# supertrack.net
KiCad netlist of a schematic drawn in EAGLE
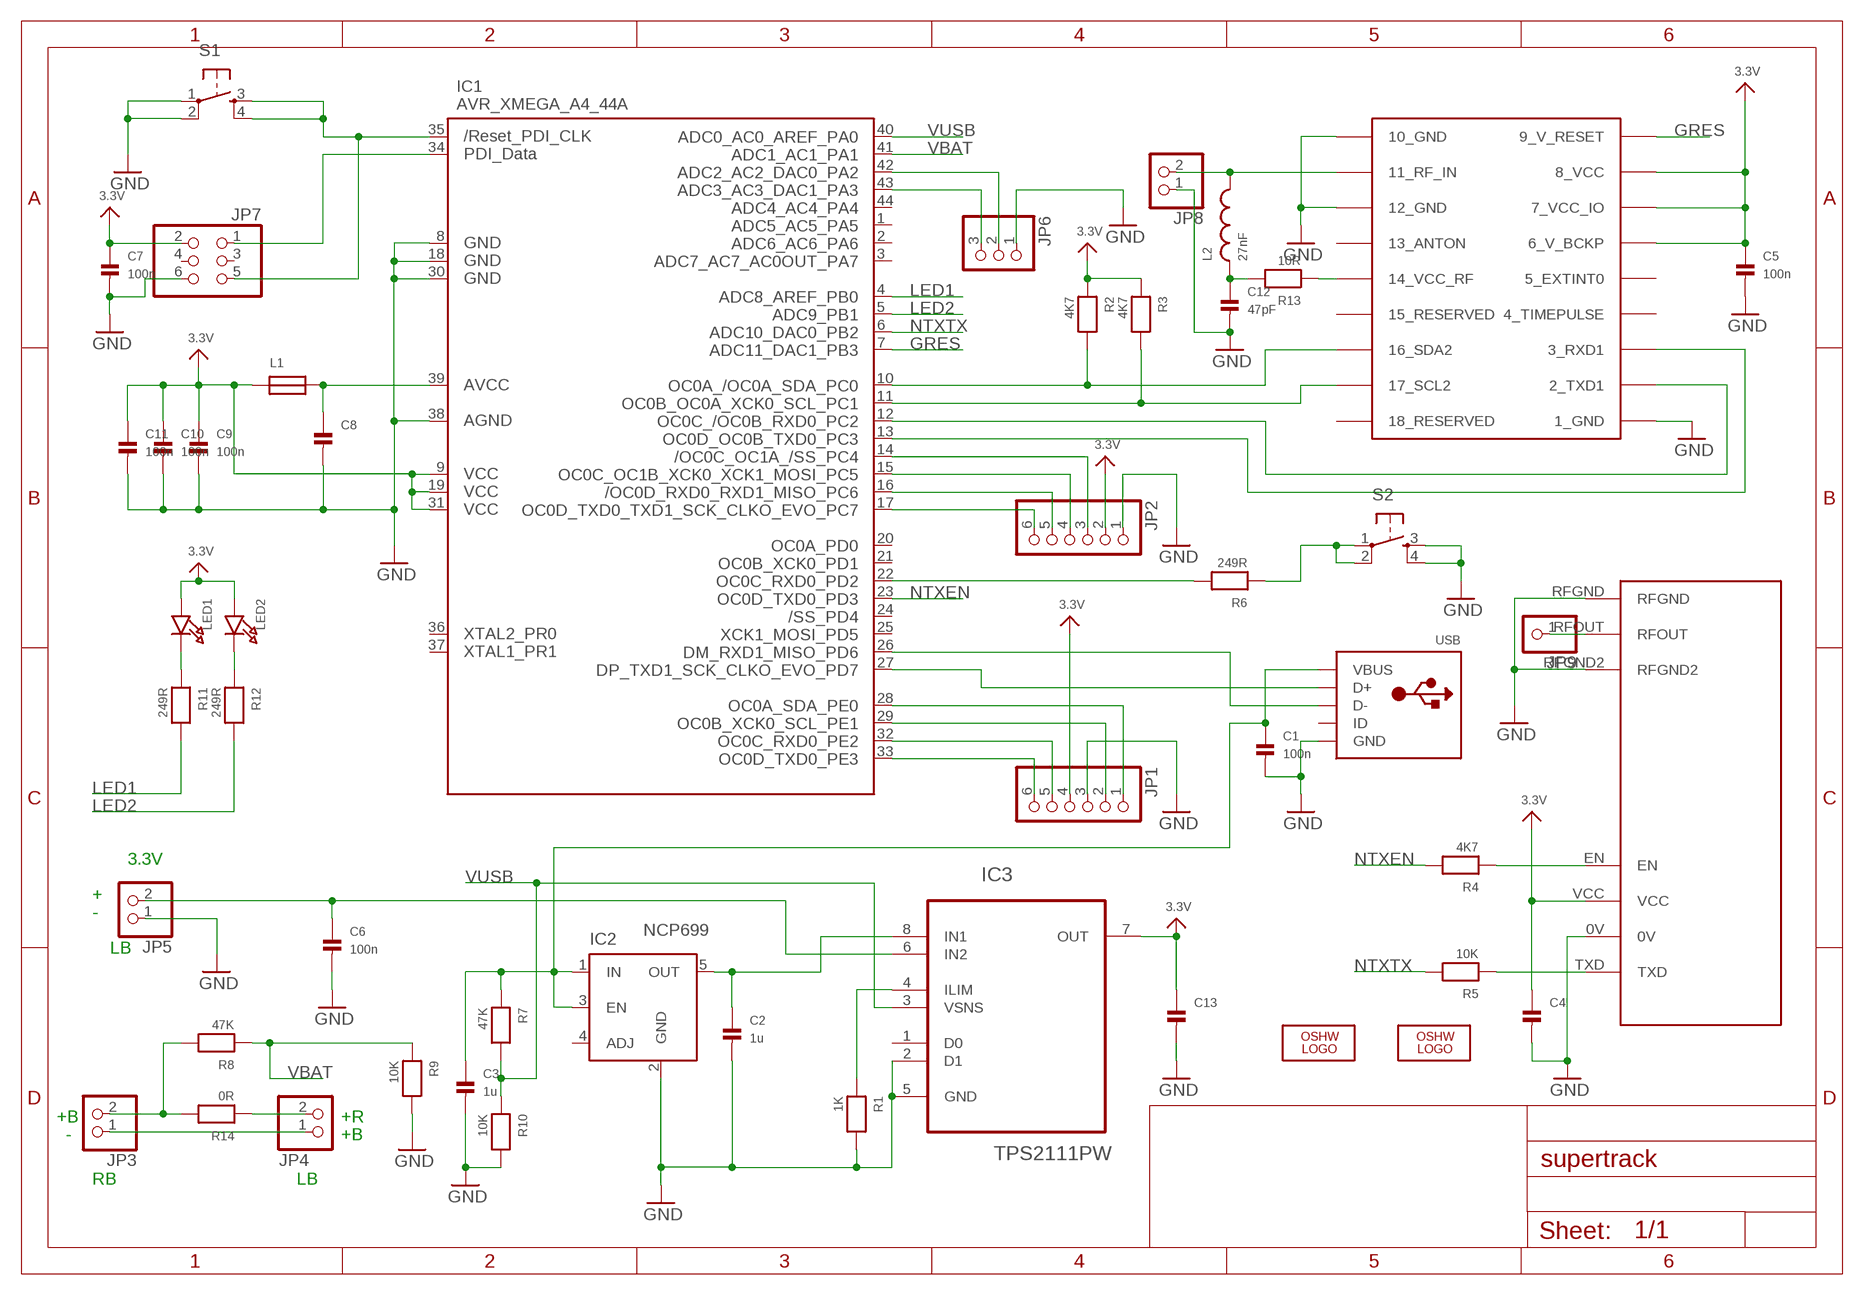
[diagram p0: schematic, sheet 1]

(export (version "E")
  (design (tool "Eeschema 10.0.6"))
  (components
    (comp (ref "C1")
      (value "100n")
      (footprint "eagle-import:0603")
      (libsource (lib "eagle-import") (part "CAP_CERAMIC0603"))
    )
    (comp (ref "C2")
      (value "1u")
      (footprint "eagle-import:0603")
      (libsource (lib "eagle-import") (part "CAP_CERAMIC0603"))
    )
    (comp (ref "C3")
      (value "1u")
      (footprint "eagle-import:0603")
      (libsource (lib "eagle-import") (part "CAP_CERAMIC0603"))
    )
    (comp (ref "C4")
      (value "CAP_CERAMIC0603")
      (footprint "eagle-import:0603")
      (libsource (lib "eagle-import") (part "CAP_CERAMIC0603"))
    )
    (comp (ref "C5")
      (value "100n")
      (footprint "eagle-import:0603")
      (libsource (lib "eagle-import") (part "CAP_CERAMIC0603"))
    )
    (comp (ref "C6")
      (value "100n")
      (footprint "eagle-import:0603")
      (libsource (lib "eagle-import") (part "CAP_CERAMIC0603"))
    )
    (comp (ref "C7")
      (value "100n")
      (footprint "eagle-import:0603")
      (libsource (lib "eagle-import") (part "CAP_CERAMIC0603"))
    )
    (comp (ref "C8")
      (value "CAP_CERAMIC0603")
      (footprint "eagle-import:0603")
      (libsource (lib "eagle-import") (part "CAP_CERAMIC0603"))
    )
    (comp (ref "C9")
      (value "100n")
      (footprint "eagle-import:0603")
      (libsource (lib "eagle-import") (part "CAP_CERAMIC0603"))
    )
    (comp (ref "C10")
      (value "100n")
      (footprint "eagle-import:0603")
      (libsource (lib "eagle-import") (part "CAP_CERAMIC0603"))
    )
    (comp (ref "C11")
      (value "100n")
      (footprint "eagle-import:0603")
      (libsource (lib "eagle-import") (part "CAP_CERAMIC0603"))
    )
    (comp (ref "C12")
      (value "47pF")
      (footprint "eagle-import:0603")
      (libsource (lib "eagle-import") (part "CAP_CERAMIC0603"))
    )
    (comp (ref "C13")
      (value "CAP_CERAMIC0603")
      (footprint "eagle-import:0603")
      (libsource (lib "eagle-import") (part "CAP_CERAMIC0603"))
    )
    (comp (ref "IC1")
      (value "AVR_XMEGA_A4_44A")
      (footprint "eagle-import:TQFP44")
      (libsource (lib "eagle-import") (part "AVR_XMEGA_A4_44A"))
    )
    (comp (ref "IC2")
      (value "NCP699")
      (footprint "eagle-import:SOT23-5")
      (fields (field (name "MF") "ALTERA CORPORATION") (field (name "MPN") "MIC5219BM5 TR"))
      (libsource (lib "eagle-import") (part "MIC5219BM5"))
    )
    (comp (ref "IC3")
      (value "TPS2111PW")
      (footprint "eagle-import:SOP65P640X120-8N")
      (libsource (lib "eagle-import") (part "TPS2111PW"))
    )
    (comp (ref "JP1")
      (value "PINHD-1X6")
      (footprint "eagle-import:1X06")
      (libsource (lib "eagle-import") (part "PINHD-1X6"))
    )
    (comp (ref "JP2")
      (value "PINHD-1X6")
      (footprint "eagle-import:1X06")
      (libsource (lib "eagle-import") (part "PINHD-1X6"))
    )
    (comp (ref "JP3")
      (value "PINHD-1X2")
      (footprint "eagle-import:1X02")
      (libsource (lib "eagle-import") (part "PINHD-1X2"))
    )
    (comp (ref "JP4")
      (value "PINHD-1X2")
      (footprint "eagle-import:1X02")
      (libsource (lib "eagle-import") (part "PINHD-1X2"))
    )
    (comp (ref "JP5")
      (value "PINHD-1X2")
      (footprint "eagle-import:1X02")
      (libsource (lib "eagle-import") (part "PINHD-1X2"))
    )
    (comp (ref "JP6")
      (value "PINHD-1X3")
      (footprint "eagle-import:1X03")
      (libsource (lib "eagle-import") (part "PINHD-1X3"))
    )
    (comp (ref "JP7")
      (value "PINHD-2X3")
      (footprint "eagle-import:2X03")
      (libsource (lib "eagle-import") (part "PINHD-2X3"))
    )
    (comp (ref "JP8")
      (value "HEADER-1X2ROUND")
      (footprint "eagle-import:1X02_ROUND")
      (libsource (lib "eagle-import") (part "HEADER-1X2ROUND"))
    )
    (comp (ref "JP9")
      (value "HEADER-1X1ROUND")
      (footprint "eagle-import:1X01_ROUND")
      (libsource (lib "eagle-import") (part "HEADER-1X1ROUND"))
    )
    (comp (ref "L1")
      (value "FERRITE")
      (footprint "eagle-import:0603")
      (libsource (lib "eagle-import") (part "FERRITE"))
    )
    (comp (ref "L2")
      (value "27nF")
      (footprint "eagle-import:0603")
      (libsource (lib "eagle-import") (part "INDUCTOR0603"))
    )
    (comp (ref "LED1")
      (value "LED0603")
      (footprint "eagle-import:CHIPLED_0603")
      (libsource (lib "eagle-import") (part "LED0603"))
    )
    (comp (ref "LED2")
      (value "LED0603")
      (footprint "eagle-import:CHIPLED_0603")
      (libsource (lib "eagle-import") (part "LED0603"))
    )
    (comp (ref "LOGO1")
      (value "OSHW_LOGO_8MILX0150-NT")
      (footprint "eagle-import:OSHW_8X150_NOTEXT")
      (libsource (lib "eagle-import") (part "OSHW_LOGO_8MILX0150-NT"))
    )
    (comp (ref "LOGO2")
      (value "OSHW_LOGO_8MILX0100-NT")
      (footprint "eagle-import:OSHW_8X100_NOTEXT")
      (libsource (lib "eagle-import") (part "OSHW_LOGO_8MILX0100-NT"))
    )
    (comp (ref "R1")
      (value "1K")
      (footprint "eagle-import:0603")
      (libsource (lib "eagle-import") (part "RESISTOR0603"))
    )
    (comp (ref "R2")
      (value "4K7")
      (footprint "eagle-import:0603")
      (libsource (lib "eagle-import") (part "RESISTOR0603"))
    )
    (comp (ref "R3")
      (value "4K7")
      (footprint "eagle-import:0603")
      (libsource (lib "eagle-import") (part "RESISTOR0603"))
    )
    (comp (ref "R4")
      (value "4K7")
      (footprint "eagle-import:0603")
      (libsource (lib "eagle-import") (part "RESISTOR0603"))
    )
    (comp (ref "R5")
      (value "10K")
      (footprint "eagle-import:0603")
      (libsource (lib "eagle-import") (part "RESISTOR0603"))
    )
    (comp (ref "R6")
      (value "249R")
      (footprint "eagle-import:0603")
      (libsource (lib "eagle-import") (part "RESISTOR0603"))
    )
    (comp (ref "R7")
      (value "47K")
      (footprint "eagle-import:0603")
      (libsource (lib "eagle-import") (part "RESISTOR0603"))
    )
    (comp (ref "R8")
      (value "47K")
      (footprint "eagle-import:0603")
      (libsource (lib "eagle-import") (part "RESISTOR0603"))
    )
    (comp (ref "R9")
      (value "10K")
      (footprint "eagle-import:0603")
      (libsource (lib "eagle-import") (part "RESISTOR0603"))
    )
    (comp (ref "R10")
      (value "10K")
      (footprint "eagle-import:0603")
      (libsource (lib "eagle-import") (part "RESISTOR0603"))
    )
    (comp (ref "R11")
      (value "249R")
      (footprint "eagle-import:0603")
      (libsource (lib "eagle-import") (part "RESISTOR0603"))
    )
    (comp (ref "R12")
      (value "249R")
      (footprint "eagle-import:0603")
      (libsource (lib "eagle-import") (part "RESISTOR0603"))
    )
    (comp (ref "R13")
      (value "10R")
      (footprint "eagle-import:0603")
      (libsource (lib "eagle-import") (part "RESISTOR0603"))
    )
    (comp (ref "R14")
      (value "0R")
      (footprint "eagle-import:0603")
      (libsource (lib "eagle-import") (part "RESISTOR0603"))
    )
    (comp (ref "S1")
      (value "TAC_SWITCHSMD")
      (footprint "eagle-import:TACTILE_SWITCH_SMD")
      (libsource (lib "eagle-import") (part "TAC_SWITCHSMD"))
    )
    (comp (ref "S2")
      (value "TAC_SWITCHSMD")
      (footprint "eagle-import:TACTILE_SWITCH_SMD")
      (libsource (lib "eagle-import") (part "TAC_SWITCHSMD"))
    )
    (comp (ref "U$1")
      (value "NTX2")
      (footprint "eagle-import:NTX2")
      (libsource (lib "eagle-import") (part "NTX2"))
    )
    (comp (ref "U$2")
      (value "UBLOX_MAX")
      (footprint "eagle-import:UBLOX_MAX")
      (libsource (lib "eagle-import") (part "UBLOX_MAX"))
    )
    (comp (ref "USB")
      (value "USBMINIB")
      (footprint "eagle-import:USB-MINIB")
      (libsource (lib "eagle-import") (part "USBMINIB"))
    )
  )
  (nets
    (net (code "1") (name "/GRES") (class "Default")
      (node (ref "IC1") (pin "7") (pinfunction "PB3_7") (pintype "bidirectional"))
      (node (ref "U$2") (pin "9_V_RESET") (pinfunction "9_V_RESET_9_V_RESET") (pintype "power_in"))
    )
    (net (code "2") (name "/LED1") (class "Default")
      (node (ref "IC1") (pin "4") (pinfunction "PB0_4") (pintype "bidirectional"))
      (node (ref "R11") (pin "2") (pinfunction "2_2") (pintype "passive"))
    )
    (net (code "3") (name "/LED2") (class "Default")
      (node (ref "IC1") (pin "5") (pinfunction "PB1_5") (pintype "bidirectional"))
      (node (ref "R12") (pin "2") (pinfunction "2_2") (pintype "passive"))
    )
    (net (code "4") (name "/NTXEN") (class "Default")
      (node (ref "IC1") (pin "23") (pinfunction "PD3_23") (pintype "bidirectional"))
      (node (ref "R4") (pin "2") (pinfunction "2_2") (pintype "passive"))
    )
    (net (code "5") (name "/NTXTX") (class "Default")
      (node (ref "IC1") (pin "6") (pinfunction "PB2_6") (pintype "bidirectional"))
      (node (ref "R5") (pin "2") (pinfunction "2_2") (pintype "passive"))
    )
    (net (code "6") (name "/VBAT") (class "Default")
      (node (ref "IC1") (pin "41") (pinfunction "PA1_41") (pintype "bidirectional"))
      (node (ref "R8") (pin "1") (pinfunction "1_1") (pintype "passive"))
      (node (ref "R9") (pin "1") (pinfunction "1_1") (pintype "passive"))
    )
    (net (code "7") (name "/VUSB") (class "Default")
      (node (ref "IC1") (pin "40") (pinfunction "PA0_40") (pintype "bidirectional"))
      (node (ref "IC3") (pin "3") (pinfunction "VSNS_3") (pintype "input"))
      (node (ref "R10") (pin "1") (pinfunction "1_1") (pintype "passive"))
      (node (ref "R7") (pin "2") (pinfunction "2_2") (pintype "passive"))
    )
    (net (code "8") (name "3.3V") (class "Default")
      (node (ref "C10") (pin "1") (pinfunction "P$1_1") (pintype "passive"))
      (node (ref "C11") (pin "1") (pinfunction "P$1_1") (pintype "passive"))
      (node (ref "C13") (pin "1") (pinfunction "P$1_1") (pintype "passive"))
      (node (ref "C4") (pin "1") (pinfunction "P$1_1") (pintype "passive"))
      (node (ref "C5") (pin "1") (pinfunction "P$1_1") (pintype "passive"))
      (node (ref "C7") (pin "1") (pinfunction "P$1_1") (pintype "passive"))
      (node (ref "C9") (pin "1") (pinfunction "P$1_1") (pintype "passive"))
      (node (ref "IC1") (pin "19") (pinfunction "VCC2_19") (pintype "bidirectional"))
      (node (ref "IC1") (pin "31") (pinfunction "VCC3_31") (pintype "bidirectional"))
      (node (ref "IC1") (pin "9") (pinfunction "VCC1_9") (pintype "bidirectional"))
      (node (ref "IC3") (pin "7") (pinfunction "OUT_7") (pintype "output"))
      (node (ref "JP1") (pin "4") (pinfunction "4_4") (pintype "passive"))
      (node (ref "JP2") (pin "2") (pinfunction "2_2") (pintype "passive"))
      (node (ref "JP7") (pin "2") (pinfunction "2_2") (pintype "passive"))
      (node (ref "L1") (pin "1") (pinfunction "P$1_1") (pintype "bidirectional"))
      (node (ref "LED1") (pin "A") (pinfunction "A_A") (pintype "passive"))
      (node (ref "LED2") (pin "A") (pinfunction "A_A") (pintype "passive"))
      (node (ref "R2") (pin "1") (pinfunction "1_1") (pintype "passive"))
      (node (ref "R3") (pin "1") (pinfunction "1_1") (pintype "passive"))
      (node (ref "U$1") (pin "VCC") (pinfunction "VCC_VCC") (pintype "bidirectional"))
      (node (ref "U$2") (pin "6_V_BCKP") (pinfunction "6_V_BCKP_6_V_BCKP") (pintype "bidirectional"))
      (node (ref "U$2") (pin "7_VCC_IO") (pinfunction "7_VCC_IO_7_VCC_IO") (pintype "power_in"))
      (node (ref "U$2") (pin "8_VCC") (pinfunction "8_VCC_8_VCC") (pintype "power_in"))
    )
    (net (code "9") (name "GND") (class "Default")
      (node (ref "C1") (pin "2") (pinfunction "P$2_2") (pintype "passive"))
      (node (ref "C10") (pin "2") (pinfunction "P$2_2") (pintype "passive"))
      (node (ref "C11") (pin "2") (pinfunction "P$2_2") (pintype "passive"))
      (node (ref "C12") (pin "2") (pinfunction "P$2_2") (pintype "passive"))
      (node (ref "C13") (pin "2") (pinfunction "P$2_2") (pintype "passive"))
      (node (ref "C2") (pin "2") (pinfunction "P$2_2") (pintype "passive"))
      (node (ref "C3") (pin "2") (pinfunction "P$2_2") (pintype "passive"))
      (node (ref "C4") (pin "2") (pinfunction "P$2_2") (pintype "passive"))
      (node (ref "C5") (pin "2") (pinfunction "P$2_2") (pintype "passive"))
      (node (ref "C6") (pin "2") (pinfunction "P$2_2") (pintype "passive"))
      (node (ref "C7") (pin "2") (pinfunction "P$2_2") (pintype "passive"))
      (node (ref "C8") (pin "2") (pinfunction "P$2_2") (pintype "passive"))
      (node (ref "C9") (pin "2") (pinfunction "P$2_2") (pintype "passive"))
      (node (ref "IC1") (pin "18") (pinfunction "GND2_18") (pintype "bidirectional"))
      (node (ref "IC1") (pin "30") (pinfunction "GND3_30") (pintype "bidirectional"))
      (node (ref "IC1") (pin "38") (pinfunction "AGND_38") (pintype "bidirectional"))
      (node (ref "IC1") (pin "8") (pinfunction "GND1_8") (pintype "bidirectional"))
      (node (ref "IC2") (pin "2") (pinfunction "GND_2") (pintype "power_in"))
      (node (ref "IC3") (pin "2") (pinfunction "D1_2") (pintype "input"))
      (node (ref "IC3") (pin "5") (pinfunction "GND_5") (pintype "passive"))
      (node (ref "JP1") (pin "3") (pinfunction "3_3") (pintype "passive"))
      (node (ref "JP2") (pin "1") (pinfunction "1_1") (pintype "passive"))
      (node (ref "JP5") (pin "1") (pinfunction "1_1") (pintype "passive"))
      (node (ref "JP6") (pin "1") (pinfunction "1_1") (pintype "passive"))
      (node (ref "JP7") (pin "6") (pinfunction "6_6") (pintype "passive"))
      (node (ref "JP8") (pin "1") (pinfunction "1_1") (pintype "passive"))
      (node (ref "R1") (pin "2") (pinfunction "2_2") (pintype "passive"))
      (node (ref "R10") (pin "2") (pinfunction "2_2") (pintype "passive"))
      (node (ref "R9") (pin "2") (pinfunction "2_2") (pintype "passive"))
      (node (ref "S1") (pin "1") (pinfunction "1_1") (pintype "passive"))
      (node (ref "S1") (pin "2") (pinfunction "2_2") (pintype "passive"))
      (node (ref "S2") (pin "3") (pinfunction "3_3") (pintype "passive"))
      (node (ref "S2") (pin "4") (pinfunction "4_4") (pintype "passive"))
      (node (ref "U$1") (pin "0V") (pinfunction "0V_0V") (pintype "bidirectional"))
      (node (ref "U$1") (pin "RFGND") (pinfunction "RFGND_RFGND") (pintype "bidirectional"))
      (node (ref "U$1") (pin "RFGND2") (pinfunction "RFGND2_RFGND2") (pintype "bidirectional"))
      (node (ref "U$2") (pin "10_GND") (pinfunction "10_GND_10_GND") (pintype "power_in"))
      (node (ref "U$2") (pin "12_GND") (pinfunction "12_GND_12_GND") (pintype "power_in"))
      (node (ref "U$2") (pin "1_GND") (pinfunction "1_GND_1_GND") (pintype "power_in"))
      (node (ref "USB") (pin "GND") (pinfunction "GND_GND") (pintype "power_in"))
    )
    (net (code "10") (name "Net-(C1-P$1)") (class "Default")
      (node (ref "C1") (pin "1") (pinfunction "P$1_1") (pintype "passive"))
      (node (ref "C3") (pin "1") (pinfunction "P$1_1") (pintype "passive"))
      (node (ref "IC2") (pin "1") (pinfunction "IN_1") (pintype "input"))
      (node (ref "IC2") (pin "3") (pinfunction "EN_3") (pintype "input"))
      (node (ref "R7") (pin "1") (pinfunction "1_1") (pintype "passive"))
      (node (ref "USB") (pin "VBUS") (pinfunction "VBUS_VBUS") (pintype "power_in"))
    )
    (net (code "11") (name "Net-(C2-P$1)") (class "Default")
      (node (ref "C2") (pin "1") (pinfunction "P$1_1") (pintype "passive"))
      (node (ref "IC2") (pin "5") (pinfunction "OUT_5") (pintype "output"))
      (node (ref "IC3") (pin "8") (pinfunction "IN1_8") (pintype "power_in"))
    )
    (net (code "12") (name "Net-(C6-P$1)") (class "Default")
      (node (ref "C6") (pin "1") (pinfunction "P$1_1") (pintype "passive"))
      (node (ref "IC3") (pin "6") (pinfunction "IN2_6") (pintype "power_in"))
      (node (ref "JP5") (pin "2") (pinfunction "2_2") (pintype "passive"))
    )
    (net (code "13") (name "Net-(C8-P$1)") (class "Default")
      (node (ref "C8") (pin "1") (pinfunction "P$1_1") (pintype "passive"))
      (node (ref "IC1") (pin "39") (pinfunction "AVCC_39") (pintype "bidirectional"))
      (node (ref "L1") (pin "2") (pinfunction "P$2_2") (pintype "bidirectional"))
    )
    (net (code "14") (name "Net-(C12-P$1)") (class "Default")
      (node (ref "C12") (pin "1") (pinfunction "P$1_1") (pintype "passive"))
      (node (ref "L2") (pin "1") (pinfunction "1_1") (pintype "passive"))
      (node (ref "R13") (pin "2") (pinfunction "2_2") (pintype "passive"))
    )
    (net (code "15") (name "Net-(IC1-PA2)") (class "Default")
      (node (ref "IC1") (pin "42") (pinfunction "PA2_42") (pintype "bidirectional"))
      (node (ref "JP6") (pin "2") (pinfunction "2_2") (pintype "passive"))
    )
    (net (code "16") (name "Net-(IC1-PA3)") (class "Default")
      (node (ref "IC1") (pin "43") (pinfunction "PA3_43") (pintype "bidirectional"))
      (node (ref "JP6") (pin "3") (pinfunction "3_3") (pintype "passive"))
    )
    (net (code "17") (name "Net-(IC1-PC0)") (class "Default")
      (node (ref "IC1") (pin "10") (pinfunction "PC0_10") (pintype "bidirectional"))
      (node (ref "R2") (pin "2") (pinfunction "2_2") (pintype "passive"))
      (node (ref "U$2") (pin "16_SDA2") (pinfunction "16_SDA2_16_SDA2") (pintype "bidirectional"))
    )
    (net (code "18") (name "Net-(IC1-PC1)") (class "Default")
      (node (ref "IC1") (pin "11") (pinfunction "PC1_11") (pintype "bidirectional"))
      (node (ref "R3") (pin "2") (pinfunction "2_2") (pintype "passive"))
      (node (ref "U$2") (pin "17_SCL2") (pinfunction "17_SCL2_17_SCL2") (pintype "bidirectional"))
    )
    (net (code "19") (name "Net-(IC1-PC2)") (class "Default")
      (node (ref "IC1") (pin "12") (pinfunction "PC2_12") (pintype "bidirectional"))
      (node (ref "U$2") (pin "2_TXD1") (pinfunction "2_TXD1_2_TXD1") (pintype "bidirectional"))
    )
    (net (code "20") (name "Net-(IC1-PC3)") (class "Default")
      (node (ref "IC1") (pin "13") (pinfunction "PC3_13") (pintype "bidirectional"))
      (node (ref "U$2") (pin "3_RXD1") (pinfunction "3_RXD1_3_RXD1") (pintype "bidirectional"))
    )
    (net (code "21") (name "Net-(IC1-PC4)") (class "Default")
      (node (ref "IC1") (pin "14") (pinfunction "PC4_14") (pintype "bidirectional"))
      (node (ref "JP2") (pin "3") (pinfunction "3_3") (pintype "passive"))
    )
    (net (code "22") (name "Net-(IC1-PC5)") (class "Default")
      (node (ref "IC1") (pin "15") (pinfunction "PC5_15") (pintype "bidirectional"))
      (node (ref "JP2") (pin "4") (pinfunction "4_4") (pintype "passive"))
    )
    (net (code "23") (name "Net-(IC1-PC6)") (class "Default")
      (node (ref "IC1") (pin "16") (pinfunction "PC6_16") (pintype "bidirectional"))
      (node (ref "JP2") (pin "5") (pinfunction "5_5") (pintype "passive"))
    )
    (net (code "24") (name "Net-(IC1-PC7)") (class "Default")
      (node (ref "IC1") (pin "17") (pinfunction "PC7_17") (pintype "bidirectional"))
      (node (ref "JP2") (pin "6") (pinfunction "6_6") (pintype "passive"))
    )
    (net (code "25") (name "Net-(IC1-PD2)") (class "Default")
      (node (ref "IC1") (pin "22") (pinfunction "PD2_22") (pintype "bidirectional"))
      (node (ref "R6") (pin "2") (pinfunction "2_2") (pintype "passive"))
    )
    (net (code "26") (name "Net-(IC1-PD6)") (class "Default")
      (node (ref "IC1") (pin "26") (pinfunction "PD6_26") (pintype "bidirectional"))
      (node (ref "USB") (pin "D-") (pinfunction "D-_D-") (pintype "bidirectional"))
    )
    (net (code "27") (name "Net-(IC1-PD7)") (class "Default")
      (node (ref "IC1") (pin "27") (pinfunction "PD7_27") (pintype "bidirectional"))
      (node (ref "USB") (pin "D+") (pinfunction "D+_D+") (pintype "bidirectional"))
    )
    (net (code "28") (name "Net-(IC1-PDI_DATA)") (class "Default")
      (node (ref "IC1") (pin "34") (pinfunction "PDI_DATA_34") (pintype "bidirectional"))
      (node (ref "JP7") (pin "1") (pinfunction "1_1") (pintype "passive"))
    )
    (net (code "29") (name "Net-(IC1-PE0)") (class "Default")
      (node (ref "IC1") (pin "28") (pinfunction "PE0_28") (pintype "bidirectional"))
      (node (ref "JP1") (pin "1") (pinfunction "1_1") (pintype "passive"))
    )
    (net (code "30") (name "Net-(IC1-PE1)") (class "Default")
      (node (ref "IC1") (pin "29") (pinfunction "PE1_29") (pintype "bidirectional"))
      (node (ref "JP1") (pin "2") (pinfunction "2_2") (pintype "passive"))
    )
    (net (code "31") (name "Net-(IC1-PE2)") (class "Default")
      (node (ref "IC1") (pin "32") (pinfunction "PE2_32") (pintype "bidirectional"))
      (node (ref "JP1") (pin "5") (pinfunction "5_5") (pintype "passive"))
    )
    (net (code "32") (name "Net-(IC1-PE3)") (class "Default")
      (node (ref "IC1") (pin "33") (pinfunction "PE3_33") (pintype "bidirectional"))
      (node (ref "JP1") (pin "6") (pinfunction "6_6") (pintype "passive"))
    )
    (net (code "33") (name "Net-(IC1-RESET)") (class "Default")
      (node (ref "IC1") (pin "35") (pinfunction "RESET_35") (pintype "bidirectional"))
      (node (ref "JP7") (pin "5") (pinfunction "5_5") (pintype "passive"))
      (node (ref "S1") (pin "3") (pinfunction "3_3") (pintype "passive"))
      (node (ref "S1") (pin "4") (pinfunction "4_4") (pintype "passive"))
    )
    (net (code "34") (name "Net-(IC3-ILIM)") (class "Default")
      (node (ref "IC3") (pin "4") (pinfunction "ILIM_4") (pintype "input"))
      (node (ref "R1") (pin "1") (pinfunction "1_1") (pintype "passive"))
    )
    (net (code "35") (name "Net-(JP3-Pad1)") (class "Default")
      (node (ref "JP3") (pin "1") (pinfunction "1_1") (pintype "passive"))
      (node (ref "JP4") (pin "1") (pinfunction "1_1") (pintype "passive"))
    )
    (net (code "36") (name "Net-(JP3-Pad2)") (class "Default")
      (node (ref "JP3") (pin "2") (pinfunction "2_2") (pintype "passive"))
      (node (ref "R14") (pin "2") (pinfunction "2_2") (pintype "passive"))
      (node (ref "R8") (pin "2") (pinfunction "2_2") (pintype "passive"))
    )
    (net (code "37") (name "Net-(JP4-Pad2)") (class "Default")
      (node (ref "JP4") (pin "2") (pinfunction "2_2") (pintype "passive"))
      (node (ref "R14") (pin "1") (pinfunction "1_1") (pintype "passive"))
    )
    (net (code "38") (name "Net-(JP8-Pad2)") (class "Default")
      (node (ref "JP8") (pin "2") (pinfunction "2_2") (pintype "passive"))
      (node (ref "L2") (pin "2") (pinfunction "2_2") (pintype "passive"))
      (node (ref "U$2") (pin "11_RF_IN") (pinfunction "11_RF_IN_11_RF_IN") (pintype "bidirectional"))
    )
    (net (code "39") (name "Net-(JP9-Pad1)") (class "Default")
      (node (ref "JP9") (pin "1") (pinfunction "1_1") (pintype "passive"))
      (node (ref "U$1") (pin "RFOUT") (pinfunction "RFOUT_RFOUT") (pintype "bidirectional"))
    )
    (net (code "40") (name "Net-(LED1-PadC)") (class "Default")
      (node (ref "LED1") (pin "C") (pinfunction "C_C") (pintype "passive"))
      (node (ref "R11") (pin "1") (pinfunction "1_1") (pintype "passive"))
    )
    (net (code "41") (name "Net-(LED2-PadC)") (class "Default")
      (node (ref "LED2") (pin "C") (pinfunction "C_C") (pintype "passive"))
      (node (ref "R12") (pin "1") (pinfunction "1_1") (pintype "passive"))
    )
    (net (code "42") (name "Net-(R4-Pad1)") (class "Default")
      (node (ref "R4") (pin "1") (pinfunction "1_1") (pintype "passive"))
      (node (ref "U$1") (pin "EN") (pinfunction "EN_EN") (pintype "bidirectional"))
    )
    (net (code "43") (name "Net-(R5-Pad1)") (class "Default")
      (node (ref "R5") (pin "1") (pinfunction "1_1") (pintype "passive"))
      (node (ref "U$1") (pin "TXD") (pinfunction "TXD_TXD") (pintype "bidirectional"))
    )
    (net (code "44") (name "Net-(R6-Pad1)") (class "Default")
      (node (ref "R6") (pin "1") (pinfunction "1_1") (pintype "passive"))
      (node (ref "S2") (pin "1") (pinfunction "1_1") (pintype "passive"))
      (node (ref "S2") (pin "2") (pinfunction "2_2") (pintype "passive"))
    )
    (net (code "45") (name "Net-(R13-Pad1)") (class "Default")
      (node (ref "R13") (pin "1") (pinfunction "1_1") (pintype "passive"))
      (node (ref "U$2") (pin "14_VCC_RF") (pinfunction "14_VCC_RF_14_VCC_RF") (pintype "bidirectional"))
    )
    (net (code "46") (name "unconnected-(IC1-PA4-Pad44)") (class "Default")
      (node (ref "IC1") (pin "44") (pinfunction "PA4_44") (pintype "bidirectional"))
    )
    (net (code "47") (name "unconnected-(IC1-PA5-Pad1)") (class "Default")
      (node (ref "IC1") (pin "1") (pinfunction "PA5_1") (pintype "bidirectional"))
    )
    (net (code "48") (name "unconnected-(IC1-PA6-Pad2)") (class "Default")
      (node (ref "IC1") (pin "2") (pinfunction "PA6_2") (pintype "bidirectional"))
    )
    (net (code "49") (name "unconnected-(IC1-PA7-Pad3)") (class "Default")
      (node (ref "IC1") (pin "3") (pinfunction "PA7_3") (pintype "bidirectional"))
    )
    (net (code "50") (name "unconnected-(IC1-PD0-Pad20)") (class "Default")
      (node (ref "IC1") (pin "20") (pinfunction "PD0_20") (pintype "bidirectional"))
    )
    (net (code "51") (name "unconnected-(IC1-PD1-Pad21)") (class "Default")
      (node (ref "IC1") (pin "21") (pinfunction "PD1_21") (pintype "bidirectional"))
    )
    (net (code "52") (name "unconnected-(IC1-PD4-Pad24)") (class "Default")
      (node (ref "IC1") (pin "24") (pinfunction "PD4_24") (pintype "bidirectional"))
    )
    (net (code "53") (name "unconnected-(IC1-PD5-Pad25)") (class "Default")
      (node (ref "IC1") (pin "25") (pinfunction "PD5_25") (pintype "bidirectional"))
    )
    (net (code "54") (name "unconnected-(IC1-PR0-Pad36)") (class "Default")
      (node (ref "IC1") (pin "36") (pinfunction "PR0_36") (pintype "bidirectional"))
    )
    (net (code "55") (name "unconnected-(IC1-PR1-Pad37)") (class "Default")
      (node (ref "IC1") (pin "37") (pinfunction "PR1_37") (pintype "bidirectional"))
    )
    (net (code "56") (name "unconnected-(IC2-ADJ-Pad4)") (class "Default")
      (node (ref "IC2") (pin "4") (pinfunction "ADJ_4") (pintype "passive"))
    )
    (net (code "57") (name "unconnected-(IC3-D0-Pad1)") (class "Default")
      (node (ref "IC3") (pin "1") (pinfunction "D0_1") (pintype "input"))
    )
    (net (code "58") (name "unconnected-(JP7-Pad3)") (class "Default")
      (node (ref "JP7") (pin "3") (pinfunction "3_3") (pintype "passive"))
    )
    (net (code "59") (name "unconnected-(JP7-Pad4)") (class "Default")
      (node (ref "JP7") (pin "4") (pinfunction "4_4") (pintype "passive"))
    )
    (net (code "60") (name "unconnected-(U$2-Pad4_TIMEPULSE)") (class "Default")
      (node (ref "U$2") (pin "4_TIMEPULSE") (pinfunction "4_TIMEPULSE_4_TIMEPULSE") (pintype "bidirectional"))
    )
    (net (code "61") (name "unconnected-(U$2-Pad5_EXTINT0)") (class "Default")
      (node (ref "U$2") (pin "5_EXTINT0") (pinfunction "5_EXTINT0_5_EXTINT0") (pintype "bidirectional"))
    )
    (net (code "62") (name "unconnected-(U$2-Pad13_ANTON)") (class "Default")
      (node (ref "U$2") (pin "13_ANTON") (pinfunction "13_ANTON_13_ANTON") (pintype "bidirectional"))
    )
    (net (code "63") (name "unconnected-(U$2-Pad15_RESERVED)") (class "Default")
      (node (ref "U$2") (pin "15_RESERVED") (pinfunction "15_RESERVED_15_RESERVED") (pintype "bidirectional"))
    )
    (net (code "64") (name "unconnected-(U$2-Pad18_RESERVED)") (class "Default")
      (node (ref "U$2") (pin "18_RESERVED") (pinfunction "18_RESERVED_18_RESERVED") (pintype "bidirectional"))
    )
    (net (code "65") (name "unconnected-(USB-PadID)") (class "Default")
      (node (ref "USB") (pin "ID") (pinfunction "ID_ID") (pintype "bidirectional"))
    )
  )
)
